# X-Bot.net
KiCad netlist of a schematic drawn in Altium Designer
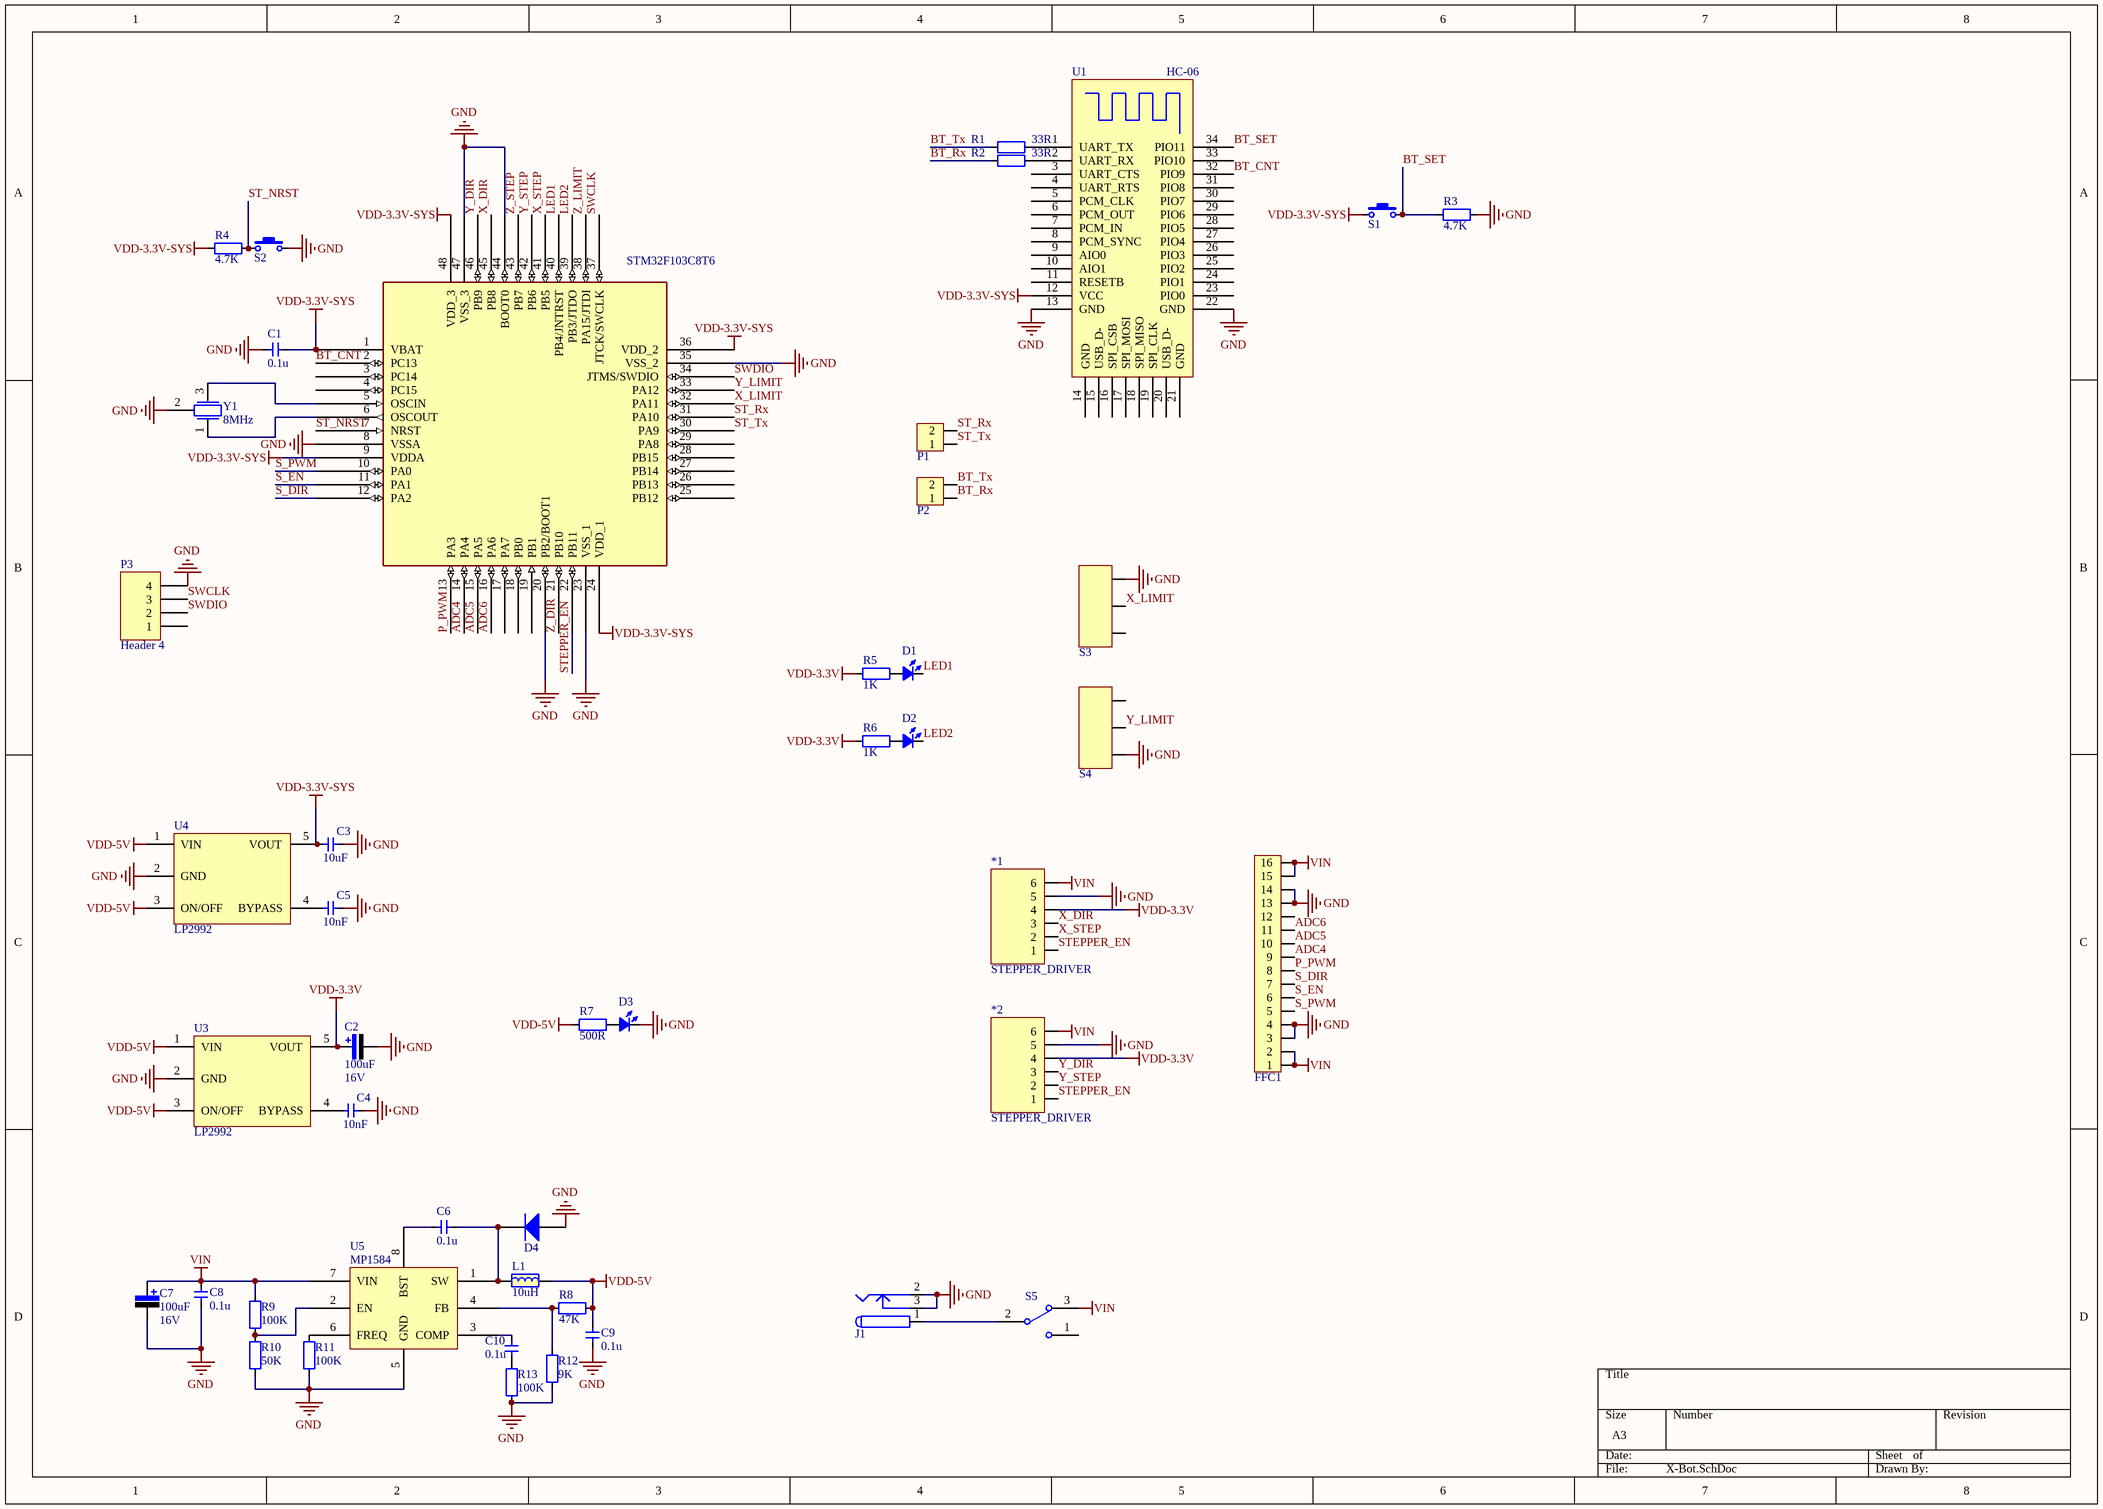
[diagram p0: X-Bot.SchDoc]

(export (version "E")
  (design (tool "Eeschema 10.0.6"))
  (components
    (comp (ref "*1")
      (value "STEPPER_DRIVER")
      (footprint "STEPPER_DRIVER")
      (libsource (lib "mLib") (part "STEPPER_DRIVER"))
    )
    (comp (ref "*2")
      (value "STEPPER_DRIVER")
      (footprint "STEPPER_DRIVER")
      (libsource (lib "mLib") (part "STEPPER_DRIVER"))
    )
    (comp (ref "C1")
      (value "0.1u")
      (footprint "mLib:0603-CAP")
      (description "Capacitor")
      (libsource (lib "mLib") (part "电容-0603"))
    )
    (comp (ref "C2")
      (value "100uF")
      (footprint "3528-CAP")
      (description "极性电解电容")
      (fields (field (name "VOL") "16V") (field (name "PUBLISHER") "Altium Limited"))
      (libsource (lib "mLib") (part "电容 3528"))
    )
    (comp (ref "C3")
      (value "10uF")
      (footprint "mLib:0603-CAP")
      (description "Capacitor")
      (libsource (lib "mLib") (part "电容-0603"))
    )
    (comp (ref "C4")
      (value "10nF")
      (footprint "mLib:0603-CAP")
      (description "Capacitor")
      (libsource (lib "mLib") (part "电容-0603"))
    )
    (comp (ref "C5")
      (value "10nF")
      (footprint "mLib:0603-CAP")
      (description "Capacitor")
      (libsource (lib "mLib") (part "电容-0603"))
    )
    (comp (ref "C6")
      (value "0.1u")
      (footprint "mLib:0603-CAP")
      (description "Capacitor")
      (libsource (lib "mLib") (part "电容-0603"))
    )
    (comp (ref "C7")
      (value "100uF")
      (footprint "3528-CAP")
      (description "极性电解电容")
      (fields (field (name "VOL") "16V") (field (name "PUBLISHER") "Altium Limited"))
      (libsource (lib "") (part "电容 3528_1"))
    )
    (comp (ref "C8")
      (value "0.1u")
      (footprint "mLib:0603-CAP")
      (description "Capacitor")
      (libsource (lib "mLib") (part "电容-0603"))
    )
    (comp (ref "C9")
      (value "0.1u")
      (footprint "mLib:0603-CAP")
      (description "Capacitor")
      (libsource (lib "mLib") (part "电容-0603"))
    )
    (comp (ref "C10")
      (value "0.1u")
      (footprint "mLib:0603-CAP")
      (description "Capacitor")
      (libsource (lib "mLib") (part "电容-0603"))
    )
    (comp (ref "D1")
      (value "LED-0603")
      (footprint "mLib:0603-LED-BLUE")
      (description "LED")
      (libsource (lib "mLib") (part "LED-0603"))
    )
    (comp (ref "D2")
      (value "LED-0603")
      (footprint "mLib:0603-LED-BLUE")
      (description "LED")
      (libsource (lib "mLib") (part "LED-0603"))
    )
    (comp (ref "D3")
      (value "LED-0603")
      (footprint "mLib:0603-LED-BLUE")
      (description "LED")
      (libsource (lib "mLib") (part "LED-0603"))
    )
    (comp (ref "D4")
      (value "二极管-5819W")
      (footprint "SOD-123")
      (description "40V")
      (libsource (lib "mLib") (part "二极管-5819W"))
    )
    (comp (ref "FFC1")
      (value "FFC_0.5_16")
      (footprint "FFC_0.5_16")
      (description "FFC")
      (libsource (lib "Integrated_Library") (part "FFC_0.5_16"))
    )
    (comp (ref "J1")
      (value "PowerJack_2.5")
      (footprint "KLD_0202")
      (description "DC Power Jack")
      (libsource (lib "Integrated_Library") (part "PowerJack_2.5"))
    )
    (comp (ref "L1")
      (value "10uH")
      (footprint "L-SMD-7")
      (description "磁珠")
      (libsource (lib "mLib") (part "电感-0805"))
    )
    (comp (ref "P1")
      (value "HDR1x2_2.54")
      (footprint "HDR1X2_2.54_180")
      (description "Header")
      (libsource (lib "Integrated_Library") (part "HDR1x2_2.54"))
    )
    (comp (ref "P2")
      (value "HDR1x2_2.54")
      (footprint "HDR1X2_2.54_180")
      (description "Header")
      (libsource (lib "Integrated_Library") (part "HDR1x2_2.54"))
    )
    (comp (ref "P3")
      (value "Header 4")
      (footprint "HDR1X4")
      (description "Header, 4-Pin")
      (fields (field (name "PUBLISHER") "Altium Limited"))
      (libsource (lib "Miscellaneous Connectors") (part "Header 4"))
    )
    (comp (ref "R1")
      (value "33R")
      (footprint "mLib:0603-RES")
      (description "Resistor")
      (libsource (lib "") (part "电阻-0603_1"))
    )
    (comp (ref "R2")
      (value "33R")
      (footprint "mLib:0603-RES")
      (description "Resistor")
      (libsource (lib "") (part "电阻-0603_1"))
    )
    (comp (ref "R3")
      (value "4.7K")
      (footprint "mLib:0603-RES")
      (description "Resistor")
      (libsource (lib "") (part "电阻-0603_2"))
    )
    (comp (ref "R4")
      (value "4.7K")
      (footprint "mLib:0603-RES")
      (description "Resistor")
      (libsource (lib "") (part "电阻-0603_2"))
    )
    (comp (ref "R5")
      (value "1K")
      (footprint "mLib:0603-RES")
      (description "Resistor")
      (libsource (lib "") (part "电阻-0603_1"))
    )
    (comp (ref "R6")
      (value "1K")
      (footprint "mLib:0603-RES")
      (description "Resistor")
      (libsource (lib "") (part "电阻-0603_1"))
    )
    (comp (ref "R7")
      (value "500R")
      (footprint "mLib:0603-RES")
      (description "Resistor")
      (libsource (lib "") (part "电阻-0603_1"))
    )
    (comp (ref "R8")
      (value "47K")
      (footprint "mLib:0603-RES")
      (description "Resistor")
      (libsource (lib "") (part "电阻-0603_2"))
    )
    (comp (ref "R9")
      (value "100K")
      (footprint "mLib:0603-RES")
      (description "Resistor")
      (libsource (lib "mLib") (part "电阻-0603"))
    )
    (comp (ref "R10")
      (value "50K")
      (footprint "mLib:0603-RES")
      (description "Resistor")
      (libsource (lib "mLib") (part "电阻-0603"))
    )
    (comp (ref "R11")
      (value "100K")
      (footprint "mLib:0603-RES")
      (description "Resistor")
      (libsource (lib "mLib") (part "电阻-0603"))
    )
    (comp (ref "R12")
      (value "9K")
      (footprint "mLib:0603-RES")
      (description "Resistor")
      (libsource (lib "mLib") (part "电阻-0603"))
    )
    (comp (ref "R13")
      (value "100K")
      (footprint "mLib:0603-RES")
      (description "Resistor")
      (libsource (lib "mLib") (part "电阻-0603"))
    )
    (comp (ref "S1")
      (value "ButtonTACT_3x4x2_180")
      (footprint "ButtonTACT_3x4x2_180H")
      (description "Button")
      (libsource (lib "Integrated_Library") (part "ButtonTACT_3x4x2_180"))
    )
    (comp (ref "S2")
      (value "ButtonTACT_3x4x2_180")
      (footprint "ButtonTACT_3x4x2_180H")
      (description "Button")
      (libsource (lib "Integrated_Library") (part "ButtonTACT_3x4x2_180"))
    )
    (comp (ref "S3")
      (value "LimitSwitch")
      (footprint "Limit Switch")
      (libsource (lib "mLib") (part "LimitSwitch"))
    )
    (comp (ref "S4")
      (value "LimitSwitch")
      (footprint "Limit Switch")
      (libsource (lib "mLib") (part "LimitSwitch"))
    )
    (comp (ref "S5")
      (value "SwitchSPDT_4.3x8.6_D90")
      (footprint "SwitchSPDT_4.3X8.6_D90")
      (description "Switch")
      (libsource (lib "Integrated_Library") (part "SwitchSPDT_4.3x8.6_D90"))
    )
    (comp (ref "U1")
      (value "HC-06")
      (footprint "蓝牙模块HC-06")
      (description "HM bluetooth module HM-01,HM-02,HM-09")
      (libsource (lib "HMSoft") (part "HM01_02_09_1"))
    )
    (comp (ref "U2")
      (value "STM32F103C8T6")
      (footprint "LQFP-48")
      (description "MCU")
      (libsource (lib "mLib") (part "STM32F103C8T6"))
    )
    (comp (ref "U3")
      (value "LP2992")
      (footprint "SOT23-5")
      (description "LDO")
      (libsource (lib "mLib") (part "LP2992"))
    )
    (comp (ref "U4")
      (value "LP2992")
      (footprint "SOT23-5")
      (description "LDO")
      (libsource (lib "mLib") (part "LP2992"))
    )
    (comp (ref "U5")
      (value "MP1584")
      (footprint "SO-8")
      (description "电源芯片")
      (libsource (lib "mLib") (part "MP1584"))
    )
    (comp (ref "Y1")
      (value "8MHz")
      (footprint "晶振-3P")
      (description "村田贴片")
      (libsource (lib "mLib") (part "晶振-3Pin"))
    )
  )
  (nets
    (net (code "1") (name "/ADC4") (class "Default")
      (node (ref "FFC1") (pin "9") (pinfunction "9_9") (pintype "passive"))
      (node (ref "U2") (pin "14") (pinfunction "PA4_14") (pintype "bidirectional"))
    )
    (net (code "2") (name "/ADC5") (class "Default")
      (node (ref "FFC1") (pin "10") (pinfunction "10_10") (pintype "passive"))
      (node (ref "U2") (pin "15") (pinfunction "PA5_15") (pintype "bidirectional"))
    )
    (net (code "3") (name "/ADC6") (class "Default")
      (node (ref "FFC1") (pin "11") (pinfunction "11_11") (pintype "passive"))
      (node (ref "U2") (pin "16") (pinfunction "PA6_16") (pintype "bidirectional"))
    )
    (net (code "4") (name "/BT_CNT") (class "Default")
      (node (ref "U1") (pin "32") (pinfunction "PIO9_32") (pintype "passive"))
      (node (ref "U2") (pin "2") (pinfunction "PC13_2") (pintype "bidirectional"))
    )
    (net (code "5") (name "/BT_Rx") (class "Default")
      (node (ref "P2") (pin "1") (pinfunction "1_1") (pintype "passive"))
      (node (ref "R2") (pin "1") (pinfunction "1_1") (pintype "passive"))
    )
    (net (code "6") (name "/BT_SET") (class "Default")
      (node (ref "R3") (pin "2") (pinfunction "2_2") (pintype "passive"))
      (node (ref "S1") (pin "2") (pinfunction "2_2") (pintype "passive"))
      (node (ref "U1") (pin "34") (pinfunction "PIO11_34") (pintype "passive"))
    )
    (net (code "7") (name "/BT_Tx") (class "Default")
      (node (ref "P2") (pin "2") (pinfunction "2_2") (pintype "passive"))
      (node (ref "R1") (pin "1") (pinfunction "1_1") (pintype "passive"))
    )
    (net (code "8") (name "/LED1") (class "Default")
      (node (ref "D1") (pin "2") (pinfunction "K_2") (pintype "passive"))
      (node (ref "U2") (pin "40") (pinfunction "PB4/JNTRST_40") (pintype "bidirectional"))
    )
    (net (code "9") (name "/LED2") (class "Default")
      (node (ref "D2") (pin "2") (pinfunction "K_2") (pintype "passive"))
      (node (ref "U2") (pin "39") (pinfunction "PB3/JTDO_39") (pintype "bidirectional"))
    )
    (net (code "10") (name "/P_PWM") (class "Default")
      (node (ref "FFC1") (pin "8") (pinfunction "8_8") (pintype "passive"))
      (node (ref "U2") (pin "13") (pinfunction "PA3_13") (pintype "bidirectional"))
    )
    (net (code "11") (name "/STEPPER_EN") (class "Default")
      (node (ref "*1") (pin "1") (pinfunction "1_1") (pintype "passive"))
      (node (ref "*2") (pin "1") (pinfunction "1_1") (pintype "passive"))
      (node (ref "U2") (pin "22") (pinfunction "PB11_22") (pintype "bidirectional"))
    )
    (net (code "12") (name "/ST_NRST") (class "Default")
      (node (ref "R4") (pin "1") (pinfunction "1_1") (pintype "passive"))
      (node (ref "S2") (pin "1") (pinfunction "1_1") (pintype "passive"))
      (node (ref "U2") (pin "7") (pinfunction "NRST_7") (pintype "input"))
    )
    (net (code "13") (name "/ST_Rx") (class "Default")
      (node (ref "P1") (pin "2") (pinfunction "2_2") (pintype "passive"))
      (node (ref "U2") (pin "31") (pinfunction "PA10_31") (pintype "bidirectional"))
    )
    (net (code "14") (name "/ST_Tx") (class "Default")
      (node (ref "P1") (pin "1") (pinfunction "1_1") (pintype "passive"))
      (node (ref "U2") (pin "30") (pinfunction "PA9_30") (pintype "bidirectional"))
    )
    (net (code "15") (name "/SWCLK") (class "Default")
      (node (ref "P3") (pin "3") (pinfunction "3_3") (pintype "passive"))
      (node (ref "U2") (pin "37") (pinfunction "JTCK/SWCLK_37") (pintype "bidirectional"))
    )
    (net (code "16") (name "/SWDIO") (class "Default")
      (node (ref "P3") (pin "2") (pinfunction "2_2") (pintype "passive"))
      (node (ref "U2") (pin "34") (pinfunction "JTMS/SWDIO_34") (pintype "bidirectional"))
    )
    (net (code "17") (name "/S_DIR") (class "Default")
      (node (ref "FFC1") (pin "7") (pinfunction "7_7") (pintype "passive"))
      (node (ref "U2") (pin "12") (pinfunction "PA2_12") (pintype "bidirectional"))
    )
    (net (code "18") (name "/S_EN") (class "Default")
      (node (ref "FFC1") (pin "6") (pinfunction "6_6") (pintype "passive"))
      (node (ref "U2") (pin "11") (pinfunction "PA1_11") (pintype "bidirectional"))
    )
    (net (code "19") (name "/S_PWM") (class "Default")
      (node (ref "FFC1") (pin "5") (pinfunction "5_5") (pintype "passive"))
      (node (ref "U2") (pin "10") (pinfunction "PA0_10") (pintype "bidirectional"))
    )
    (net (code "20") (name "/X_DIR") (class "Default")
      (node (ref "*1") (pin "3") (pinfunction "3_3") (pintype "passive"))
      (node (ref "U2") (pin "45") (pinfunction "PB8_45") (pintype "bidirectional"))
    )
    (net (code "21") (name "/X_LIMIT") (class "Default")
      (node (ref "S3") (pin "2") (pintype "power_in"))
      (node (ref "U2") (pin "32") (pinfunction "PA11_32") (pintype "bidirectional"))
    )
    (net (code "22") (name "/X_STEP") (class "Default")
      (node (ref "*1") (pin "2") (pinfunction "2_2") (pintype "passive"))
      (node (ref "U2") (pin "41") (pinfunction "PB5_41") (pintype "bidirectional"))
    )
    (net (code "23") (name "/Y_DIR") (class "Default")
      (node (ref "*2") (pin "3") (pinfunction "3_3") (pintype "passive"))
      (node (ref "U2") (pin "46") (pinfunction "PB9_46") (pintype "bidirectional"))
    )
    (net (code "24") (name "/Y_LIMIT") (class "Default")
      (node (ref "S4") (pin "2") (pintype "power_in"))
      (node (ref "U2") (pin "33") (pinfunction "PA12_33") (pintype "bidirectional"))
    )
    (net (code "25") (name "/Y_STEP") (class "Default")
      (node (ref "*2") (pin "2") (pinfunction "2_2") (pintype "passive"))
      (node (ref "U2") (pin "42") (pinfunction "PB6_42") (pintype "bidirectional"))
    )
    (net (code "26") (name "/Z_DIR") (class "Default")
      (node (ref "U2") (pin "21") (pinfunction "PB10_21") (pintype "bidirectional"))
    )
    (net (code "27") (name "/Z_LIMIT") (class "Default")
      (node (ref "U2") (pin "38") (pinfunction "PA15/JTDI_38") (pintype "bidirectional"))
    )
    (net (code "28") (name "/Z_STEP") (class "Default")
      (node (ref "U2") (pin "43") (pinfunction "PB7_43") (pintype "bidirectional"))
    )
    (net (code "29") (name "GND") (class "Default")
      (node (ref "*1") (pin "5") (pinfunction "5_5") (pintype "passive"))
      (node (ref "*2") (pin "5") (pinfunction "5_5") (pintype "passive"))
      (node (ref "C1") (pin "1") (pinfunction "1_1") (pintype "passive"))
      (node (ref "C2") (pin "2") (pinfunction "2_2") (pintype "passive"))
      (node (ref "C3") (pin "1") (pinfunction "1_1") (pintype "passive"))
      (node (ref "C4") (pin "1") (pinfunction "1_1") (pintype "passive"))
      (node (ref "C5") (pin "1") (pinfunction "1_1") (pintype "passive"))
      (node (ref "C7") (pin "2") (pinfunction "2_2") (pintype "passive"))
      (node (ref "C8") (pin "1") (pinfunction "1_1") (pintype "passive"))
      (node (ref "C9") (pin "2") (pinfunction "2_2") (pintype "passive"))
      (node (ref "D3") (pin "2") (pinfunction "K_2") (pintype "passive"))
      (node (ref "D4") (pin "1") (pinfunction "A_1") (pintype "passive"))
      (node (ref "FFC1") (pin "13") (pinfunction "13_13") (pintype "passive"))
      (node (ref "FFC1") (pin "14") (pinfunction "14_14") (pintype "passive"))
      (node (ref "FFC1") (pin "3") (pinfunction "3_3") (pintype "passive"))
      (node (ref "FFC1") (pin "4") (pinfunction "4_4") (pintype "passive"))
      (node (ref "J1") (pin "2") (pinfunction "2_2") (pintype "power_in"))
      (node (ref "J1") (pin "3") (pinfunction "3_3") (pintype "power_in"))
      (node (ref "P3") (pin "4") (pinfunction "4_4") (pintype "passive"))
      (node (ref "R10") (pin "1") (pinfunction "1_1") (pintype "passive"))
      (node (ref "R11") (pin "1") (pinfunction "1_1") (pintype "passive"))
      (node (ref "R12") (pin "1") (pinfunction "1_1") (pintype "passive"))
      (node (ref "R13") (pin "1") (pinfunction "1_1") (pintype "passive"))
      (node (ref "R3") (pin "1") (pinfunction "1_1") (pintype "passive"))
      (node (ref "S2") (pin "2") (pinfunction "2_2") (pintype "passive"))
      (node (ref "S3") (pin "3") (pintype "power_in"))
      (node (ref "S4") (pin "1") (pintype "power_in"))
      (node (ref "U1") (pin "13") (pinfunction "GND_13") (pintype "passive"))
      (node (ref "U1") (pin "22") (pinfunction "GND_22") (pintype "passive"))
      (node (ref "U2") (pin "20") (pinfunction "PB2/BOOT1_20") (pintype "bidirectional"))
      (node (ref "U2") (pin "23") (pinfunction "VSS_1_23") (pintype "power_in"))
      (node (ref "U2") (pin "35") (pinfunction "VSS_2_35") (pintype "power_in"))
      (node (ref "U2") (pin "44") (pinfunction "BOOT0_44") (pintype "bidirectional"))
      (node (ref "U2") (pin "47") (pinfunction "VSS_3_47") (pintype "power_in"))
      (node (ref "U2") (pin "8") (pinfunction "VSSA_8") (pintype "power_in"))
      (node (ref "U3") (pin "2") (pinfunction "GND_2") (pintype "passive"))
      (node (ref "U4") (pin "2") (pinfunction "GND_2") (pintype "passive"))
      (node (ref "U5") (pin "5") (pinfunction "GND_5") (pintype "passive"))
      (node (ref "Y1") (pin "2") (pinfunction "2_2") (pintype "passive"))
    )
    (net (code "30") (name "Net-(C10-Pad1)") (class "Default")
      (node (ref "C10") (pin "1") (pinfunction "1_1") (pintype "passive"))
      (node (ref "R13") (pin "2") (pinfunction "2_2") (pintype "passive"))
    )
    (net (code "31") (name "Net-(D1-A)") (class "Default")
      (node (ref "D1") (pin "1") (pinfunction "A_1") (pintype "passive"))
      (node (ref "R5") (pin "2") (pinfunction "2_2") (pintype "passive"))
    )
    (net (code "32") (name "Net-(D2-A)") (class "Default")
      (node (ref "D2") (pin "1") (pinfunction "A_1") (pintype "passive"))
      (node (ref "R6") (pin "2") (pinfunction "2_2") (pintype "passive"))
    )
    (net (code "33") (name "Net-(D3-A)") (class "Default")
      (node (ref "D3") (pin "1") (pinfunction "A_1") (pintype "passive"))
      (node (ref "R7") (pin "2") (pinfunction "2_2") (pintype "passive"))
    )
    (net (code "34") (name "Net-(D4-K)") (class "Default")
      (node (ref "C6") (pin "2") (pinfunction "2_2") (pintype "passive"))
      (node (ref "D4") (pin "2") (pinfunction "K_2") (pintype "passive"))
      (node (ref "L1") (pin "1") (pintype "passive"))
      (node (ref "U5") (pin "1") (pinfunction "SW_1") (pintype "passive"))
    )
    (net (code "35") (name "Net-(J1-Pad1)") (class "Default")
      (node (ref "J1") (pin "1") (pinfunction "1_1") (pintype "power_in"))
      (node (ref "S5") (pin "2") (pinfunction "2_2") (pintype "passive"))
    )
    (net (code "36") (name "Net-(U1-UART_RX)") (class "Default")
      (node (ref "R2") (pin "2") (pinfunction "2_2") (pintype "passive"))
      (node (ref "U1") (pin "2") (pinfunction "UART_RX_2") (pintype "passive"))
    )
    (net (code "37") (name "Net-(U1-UART_TX)") (class "Default")
      (node (ref "R1") (pin "2") (pinfunction "2_2") (pintype "passive"))
      (node (ref "U1") (pin "1") (pinfunction "UART_TX_1") (pintype "passive"))
    )
    (net (code "38") (name "Net-(U2-OSCIN)") (class "Default")
      (node (ref "U2") (pin "5") (pinfunction "OSCIN_5") (pintype "input"))
      (node (ref "Y1") (pin "3") (pinfunction "3_3") (pintype "passive"))
    )
    (net (code "39") (name "Net-(U2-OSCOUT)") (class "Default")
      (node (ref "U2") (pin "6") (pinfunction "OSCOUT_6") (pintype "output"))
      (node (ref "Y1") (pin "1") (pinfunction "1_1") (pintype "passive"))
    )
    (net (code "40") (name "Net-(U3-BYPASS)") (class "Default")
      (node (ref "C4") (pin "2") (pinfunction "2_2") (pintype "passive"))
      (node (ref "U3") (pin "4") (pinfunction "BYPASS_4") (pintype "passive"))
    )
    (net (code "41") (name "Net-(U4-BYPASS)") (class "Default")
      (node (ref "C5") (pin "2") (pinfunction "2_2") (pintype "passive"))
      (node (ref "U4") (pin "4") (pinfunction "BYPASS_4") (pintype "passive"))
    )
    (net (code "42") (name "Net-(U5-BST)") (class "Default")
      (node (ref "C6") (pin "1") (pinfunction "1_1") (pintype "passive"))
      (node (ref "U5") (pin "8") (pinfunction "BST_8") (pintype "passive"))
    )
    (net (code "43") (name "Net-(U5-COMP)") (class "Default")
      (node (ref "C10") (pin "2") (pinfunction "2_2") (pintype "passive"))
      (node (ref "U5") (pin "3") (pinfunction "COMP_3") (pintype "passive"))
    )
    (net (code "44") (name "Net-(U5-EN)") (class "Default")
      (node (ref "R10") (pin "2") (pinfunction "2_2") (pintype "passive"))
      (node (ref "R9") (pin "1") (pinfunction "1_1") (pintype "passive"))
      (node (ref "U5") (pin "2") (pinfunction "EN_2") (pintype "passive"))
    )
    (net (code "45") (name "Net-(U5-FB)") (class "Default")
      (node (ref "R12") (pin "2") (pinfunction "2_2") (pintype "passive"))
      (node (ref "R8") (pin "2") (pinfunction "2_2") (pintype "passive"))
      (node (ref "U5") (pin "4") (pinfunction "FB_4") (pintype "passive"))
    )
    (net (code "46") (name "Net-(U5-FREQ)") (class "Default")
      (node (ref "R11") (pin "2") (pinfunction "2_2") (pintype "passive"))
      (node (ref "U5") (pin "6") (pinfunction "FREQ_6") (pintype "passive"))
    )
    (net (code "47") (name "VDD-3.3V") (class "Default")
      (node (ref "*1") (pin "4") (pinfunction "4_4") (pintype "passive"))
      (node (ref "*2") (pin "4") (pinfunction "4_4") (pintype "passive"))
      (node (ref "C2") (pin "1") (pinfunction "1_1") (pintype "passive"))
      (node (ref "R5") (pin "1") (pinfunction "1_1") (pintype "passive"))
      (node (ref "R6") (pin "1") (pinfunction "1_1") (pintype "passive"))
      (node (ref "U3") (pin "5") (pinfunction "VOUT_5") (pintype "passive"))
    )
    (net (code "48") (name "VDD-3.3V-SYS") (class "Default")
      (node (ref "C1") (pin "2") (pinfunction "2_2") (pintype "passive"))
      (node (ref "C3") (pin "2") (pinfunction "2_2") (pintype "passive"))
      (node (ref "R4") (pin "2") (pinfunction "2_2") (pintype "passive"))
      (node (ref "S1") (pin "1") (pinfunction "1_1") (pintype "passive"))
      (node (ref "U1") (pin "12") (pinfunction "VCC_12") (pintype "passive"))
      (node (ref "U2") (pin "1") (pinfunction "VBAT_1") (pintype "power_in"))
      (node (ref "U2") (pin "24") (pinfunction "VDD_1_24") (pintype "power_in"))
      (node (ref "U2") (pin "36") (pinfunction "VDD_2_36") (pintype "power_in"))
      (node (ref "U2") (pin "48") (pinfunction "VDD_3_48") (pintype "power_in"))
      (node (ref "U2") (pin "9") (pinfunction "VDDA_9") (pintype "power_in"))
      (node (ref "U4") (pin "5") (pinfunction "VOUT_5") (pintype "passive"))
    )
    (net (code "49") (name "VDD-5V") (class "Default")
      (node (ref "C9") (pin "1") (pinfunction "1_1") (pintype "passive"))
      (node (ref "L1") (pin "2") (pinfunction "2_2") (pintype "passive"))
      (node (ref "R7") (pin "1") (pinfunction "1_1") (pintype "passive"))
      (node (ref "R8") (pin "1") (pinfunction "1_1") (pintype "passive"))
      (node (ref "U3") (pin "1") (pinfunction "VIN_1") (pintype "passive"))
      (node (ref "U3") (pin "3") (pinfunction "ON/OFF_3") (pintype "passive"))
      (node (ref "U4") (pin "1") (pinfunction "VIN_1") (pintype "passive"))
      (node (ref "U4") (pin "3") (pinfunction "ON/OFF_3") (pintype "passive"))
    )
    (net (code "50") (name "VIN") (class "Default")
      (node (ref "*1") (pin "6") (pinfunction "6_6") (pintype "passive"))
      (node (ref "*2") (pin "6") (pinfunction "6_6") (pintype "passive"))
      (node (ref "C7") (pin "1") (pinfunction "1_1") (pintype "passive"))
      (node (ref "C8") (pin "2") (pinfunction "2_2") (pintype "passive"))
      (node (ref "FFC1") (pin "1") (pinfunction "1_1") (pintype "passive"))
      (node (ref "FFC1") (pin "15") (pinfunction "15_15") (pintype "passive"))
      (node (ref "FFC1") (pin "16") (pinfunction "16_16") (pintype "passive"))
      (node (ref "FFC1") (pin "2") (pinfunction "2_2") (pintype "passive"))
      (node (ref "R9") (pin "2") (pinfunction "2_2") (pintype "passive"))
      (node (ref "S5") (pin "3") (pinfunction "3_3") (pintype "passive"))
      (node (ref "U5") (pin "7") (pinfunction "VIN_7") (pintype "passive"))
    )
    (net (code "51") (name "unconnected-(FFC1-Pad12)") (class "Default")
      (node (ref "FFC1") (pin "12") (pinfunction "12_12") (pintype "passive"))
    )
    (net (code "52") (name "unconnected-(P3-Pad1)") (class "Default")
      (node (ref "P3") (pin "1") (pinfunction "1_1") (pintype "passive"))
    )
    (net (code "53") (name "unconnected-(S3-Pad1)") (class "Default")
      (node (ref "S3") (pin "1") (pintype "power_in"))
    )
    (net (code "54") (name "unconnected-(S4-Pad3)") (class "Default")
      (node (ref "S4") (pin "3") (pintype "power_in"))
    )
    (net (code "55") (name "unconnected-(S5-Pad1)") (class "Default")
      (node (ref "S5") (pin "1") (pinfunction "1_1") (pintype "passive"))
    )
    (net (code "56") (name "unconnected-(U1-AIO0-Pad9)") (class "Default")
      (node (ref "U1") (pin "9") (pinfunction "AIO0_9") (pintype "passive"))
    )
    (net (code "57") (name "unconnected-(U1-AIO1-Pad10)") (class "Default")
      (node (ref "U1") (pin "10") (pinfunction "AIO1_10") (pintype "passive"))
    )
    (net (code "58") (name "unconnected-(U1-GND-Pad14)") (class "Default")
      (node (ref "U1") (pin "14") (pinfunction "GND_14") (pintype "passive"))
    )
    (net (code "59") (name "unconnected-(U1-GND-Pad21)") (class "Default")
      (node (ref "U1") (pin "21") (pinfunction "GND_21") (pintype "passive"))
    )
    (net (code "60") (name "unconnected-(U1-PCM_CLK-Pad5)") (class "Default")
      (node (ref "U1") (pin "5") (pinfunction "PCM_CLK_5") (pintype "passive"))
    )
    (net (code "61") (name "unconnected-(U1-PCM_IN-Pad7)") (class "Default")
      (node (ref "U1") (pin "7") (pinfunction "PCM_IN_7") (pintype "passive"))
    )
    (net (code "62") (name "unconnected-(U1-PCM_OUT-Pad6)") (class "Default")
      (node (ref "U1") (pin "6") (pinfunction "PCM_OUT_6") (pintype "passive"))
    )
    (net (code "63") (name "unconnected-(U1-PCM_SYNC-Pad8)") (class "Default")
      (node (ref "U1") (pin "8") (pinfunction "PCM_SYNC_8") (pintype "passive"))
    )
    (net (code "64") (name "unconnected-(U1-PIO0-Pad23)") (class "Default")
      (node (ref "U1") (pin "23") (pinfunction "PIO0_23") (pintype "passive"))
    )
    (net (code "65") (name "unconnected-(U1-PIO1-Pad24)") (class "Default")
      (node (ref "U1") (pin "24") (pinfunction "PIO1_24") (pintype "passive"))
    )
    (net (code "66") (name "unconnected-(U1-PIO2-Pad25)") (class "Default")
      (node (ref "U1") (pin "25") (pinfunction "PIO2_25") (pintype "passive"))
    )
    (net (code "67") (name "unconnected-(U1-PIO3-Pad26)") (class "Default")
      (node (ref "U1") (pin "26") (pinfunction "PIO3_26") (pintype "passive"))
    )
    (net (code "68") (name "unconnected-(U1-PIO4-Pad27)") (class "Default")
      (node (ref "U1") (pin "27") (pinfunction "PIO4_27") (pintype "passive"))
    )
    (net (code "69") (name "unconnected-(U1-PIO5-Pad28)") (class "Default")
      (node (ref "U1") (pin "28") (pinfunction "PIO5_28") (pintype "passive"))
    )
    (net (code "70") (name "unconnected-(U1-PIO6-Pad29)") (class "Default")
      (node (ref "U1") (pin "29") (pinfunction "PIO6_29") (pintype "passive"))
    )
    (net (code "71") (name "unconnected-(U1-PIO7-Pad30)") (class "Default")
      (node (ref "U1") (pin "30") (pinfunction "PIO7_30") (pintype "passive"))
    )
    (net (code "72") (name "unconnected-(U1-PIO8-Pad31)") (class "Default")
      (node (ref "U1") (pin "31") (pinfunction "PIO8_31") (pintype "passive"))
    )
    (net (code "73") (name "unconnected-(U1-PIO10-Pad33)") (class "Default")
      (node (ref "U1") (pin "33") (pinfunction "PIO10_33") (pintype "passive"))
    )
    (net (code "74") (name "unconnected-(U1-RESETB-Pad11)") (class "Default")
      (node (ref "U1") (pin "11") (pinfunction "RESETB_11") (pintype "passive"))
    )
    (net (code "75") (name "unconnected-(U1-SPI_CLK-Pad19)") (class "Default")
      (node (ref "U1") (pin "19") (pinfunction "SPI_CLK_19") (pintype "passive"))
    )
    (net (code "76") (name "unconnected-(U1-SPI_CSB-Pad16)") (class "Default")
      (node (ref "U1") (pin "16") (pinfunction "SPI_CSB_16") (pintype "passive"))
    )
    (net (code "77") (name "unconnected-(U1-SPI_MISO-Pad18)") (class "Default")
      (node (ref "U1") (pin "18") (pinfunction "SPI_MISO_18") (pintype "passive"))
    )
    (net (code "78") (name "unconnected-(U1-SPI_MOSI-Pad17)") (class "Default")
      (node (ref "U1") (pin "17") (pinfunction "SPI_MOSI_17") (pintype "passive"))
    )
    (net (code "79") (name "unconnected-(U1-UART_CTS-Pad3)") (class "Default")
      (node (ref "U1") (pin "3") (pinfunction "UART_CTS_3") (pintype "passive"))
    )
    (net (code "80") (name "unconnected-(U1-UART_RTS-Pad4)") (class "Default")
      (node (ref "U1") (pin "4") (pinfunction "UART_RTS_4") (pintype "passive"))
    )
    (net (code "81") (name "unconnected-(U1-USB_D--Pad15)") (class "Default")
      (node (ref "U1") (pin "15") (pinfunction "USB_D-_15") (pintype "passive"))
    )
    (net (code "82") (name "unconnected-(U1-USB_D--Pad20)") (class "Default")
      (node (ref "U1") (pin "20") (pinfunction "USB_D-_20") (pintype "passive"))
    )
    (net (code "83") (name "unconnected-(U2-PA7-Pad17)") (class "Default")
      (node (ref "U2") (pin "17") (pinfunction "PA7_17") (pintype "bidirectional"))
    )
    (net (code "84") (name "unconnected-(U2-PA8-Pad29)") (class "Default")
      (node (ref "U2") (pin "29") (pinfunction "PA8_29") (pintype "bidirectional"))
    )
    (net (code "85") (name "unconnected-(U2-PB0-Pad18)") (class "Default")
      (node (ref "U2") (pin "18") (pinfunction "PB0_18") (pintype "bidirectional"))
    )
    (net (code "86") (name "unconnected-(U2-PB1-Pad19)") (class "Default")
      (node (ref "U2") (pin "19") (pinfunction "PB1_19") (pintype "input"))
    )
    (net (code "87") (name "unconnected-(U2-PB12-Pad25)") (class "Default")
      (node (ref "U2") (pin "25") (pinfunction "PB12_25") (pintype "bidirectional"))
    )
    (net (code "88") (name "unconnected-(U2-PB13-Pad26)") (class "Default")
      (node (ref "U2") (pin "26") (pinfunction "PB13_26") (pintype "bidirectional"))
    )
    (net (code "89") (name "unconnected-(U2-PB14-Pad27)") (class "Default")
      (node (ref "U2") (pin "27") (pinfunction "PB14_27") (pintype "bidirectional"))
    )
    (net (code "90") (name "unconnected-(U2-PB15-Pad28)") (class "Default")
      (node (ref "U2") (pin "28") (pinfunction "PB15_28") (pintype "bidirectional"))
    )
    (net (code "91") (name "unconnected-(U2-PC14-Pad3)") (class "Default")
      (node (ref "U2") (pin "3") (pinfunction "PC14_3") (pintype "bidirectional"))
    )
    (net (code "92") (name "unconnected-(U2-PC15-Pad4)") (class "Default")
      (node (ref "U2") (pin "4") (pinfunction "PC15_4") (pintype "bidirectional"))
    )
  )
)
